# PowerRails.net
KiCad netlist of a schematic drawn in Altium Designer
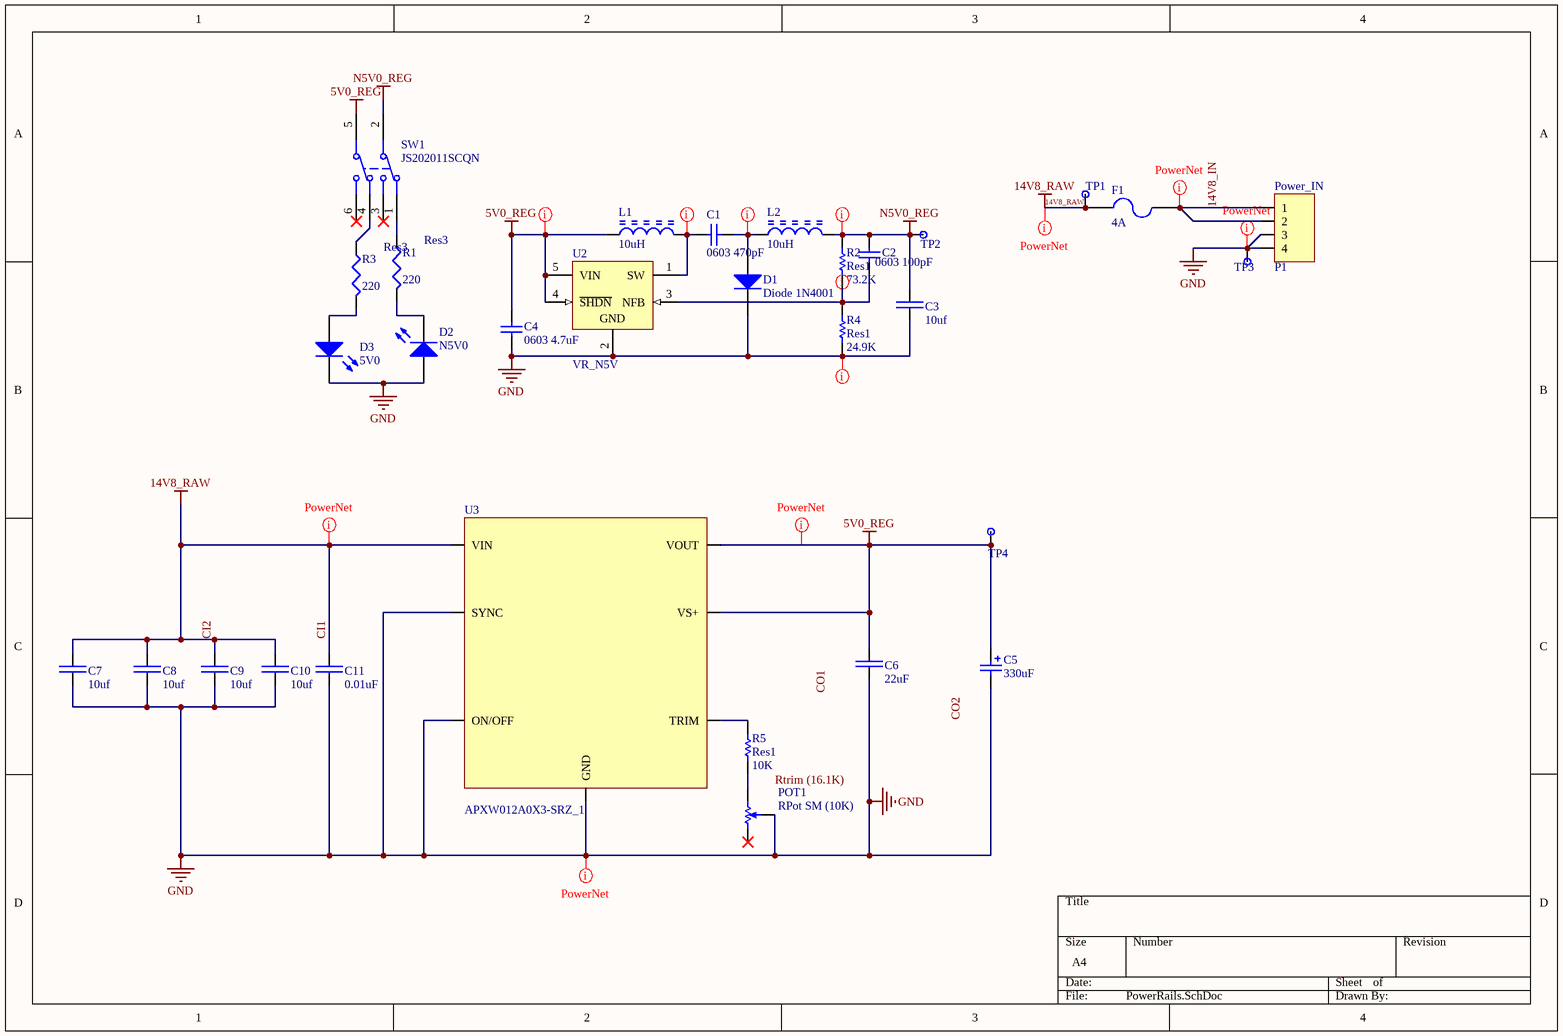
[diagram p0: PowerRails.SchDoc]

(export (version "E")
  (design (tool "Eeschema 10.0.6"))
  (components
    (comp (ref "C1")
      (value "0603 470pF")
      (footprint "CAPC1608X90X35LL10T15")
      (fields (field (name "PART NUMBER") "GRM188R61E475KE11D") (field (name "MANUFACTURER") "Murata"))
      (libsource (lib "Altium Content Vault") (part "CAP"))
    )
    (comp (ref "C2")
      (value "0603 100pF")
      (footprint "CAPC1608X90X35LL10T15")
      (fields (field (name "PART NUMBER") "GRM188R61E475KE11D") (field (name "MANUFACTURER") "Murata"))
      (libsource (lib "Altium Content Vault") (part "CAP"))
    )
    (comp (ref "C3")
      (value "10uf")
      (footprint "10uF capacitor LPB")
      (description "CAP CER 10UF 50V X5R 1206")
      (fields (field (name "TOLERANCE") "20%"))
      (libsource (lib "RSX_Capacitors") (part "GRT31CR61H106ME01L"))
    )
    (comp (ref "C4")
      (value "0603 4.7uF")
      (footprint "CAPC1608X90X35LL10T15")
      (fields (field (name "PART NUMBER") "GRM188R61E475KE11D") (field (name "MANUFACTURER") "Murata"))
      (libsource (lib "Altium Content Vault") (part "CAP"))
    )
    (comp (ref "C5")
      (value "330uF")
      (footprint "330uF throught hole")
      (description "CAP ALUM 330UF 20% 35V RADIAL")
      (fields (field (name "TOLERANCE") "20%"))
      (libsource (lib "RSX_Capacitors") (part "35ZLH330MEFCT810X12.5"))
    )
    (comp (ref "C6")
      (value "22uF")
      (footprint "22uF Capacitor")
      (description "Cap Ceramic 22uF 25V X7R 10% SMD 1210 125C Embossed T/R")
      (fields (field (name "TOLERANCE") "10%") (field (name "VOLTAGE") "25V"))
      (libsource (lib "RSX_Capacitors") (part "GRM32ER71E226KE15L"))
    )
    (comp (ref "C7")
      (value "10uf")
      (footprint "10uF capacitor LPB")
      (description "CAP CER 10UF 50V X5R 1206")
      (fields (field (name "TOLERANCE") "20%"))
      (libsource (lib "RSX_Capacitors") (part "GRT31CR61H106ME01L"))
    )
    (comp (ref "C8")
      (value "10uf")
      (footprint "10uF capacitor LPB")
      (description "CAP CER 10UF 50V X5R 1206")
      (fields (field (name "TOLERANCE") "20%"))
      (libsource (lib "RSX_Capacitors") (part "GRT31CR61H106ME01L"))
    )
    (comp (ref "C9")
      (value "10uf")
      (footprint "10uF capacitor LPB")
      (description "CAP CER 10UF 50V X5R 1206")
      (fields (field (name "TOLERANCE") "20%"))
      (libsource (lib "RSX_Capacitors") (part "GRT31CR61H106ME01L"))
    )
    (comp (ref "C10")
      (value "10uf")
      (footprint "10uF capacitor LPB")
      (description "CAP CER 10UF 50V X5R 1206")
      (fields (field (name "TOLERANCE") "20%"))
      (libsource (lib "RSX_Capacitors") (part "GRT31CR61H106ME01L"))
    )
    (comp (ref "C11")
      (value "0.01uF")
      (footprint "0.01uF capacitor")
      (description "Cap Ceramic 0.01uF 250V X7R 10% Pad SMD 0603 125C Automotive T/R")
      (fields (field (name "TOLERANCE") "10%"))
      (libsource (lib "RSX_Capacitors") (part "C0603C103KARACAUTO"))
    )
    (comp (ref "D1")
      (value "Diode 1N4001")
      (footprint "DO-41")
      (description "1 Amp General Purpose Rectifier")
      (fields (field (name "PUBLISHER") "Altium Limited"))
      (libsource (lib "Miscellaneous Devices") (part "Diode 1N4001"))
    )
    (comp (ref "D2")
      (value "N5V0")
      (footprint "LTST-C171TBKT")
      (libsource (lib "RSX_Diodes") (part "Blue LED"))
    )
    (comp (ref "D3")
      (value "5V0")
      (footprint "LTST-C171TBKT")
      (libsource (lib "RSX_Diodes") (part "Blue LED"))
    )
    (comp (ref "F1")
      (value "4A")
      (footprint "0157010.DR")
      (description "Fuse")
      (fields (field (name "PUBLISHER") "Altium Limited"))
      (libsource (lib "RSX_Miscellaneous") (part "Fuse 2"))
    )
    (comp (ref "L1")
      (value "10uH")
      (footprint "BOUR-CM322522_V")
      (description "Chip Inductor\r\n, 10 uH, +/- 10%, -40 to 125 degC, 1210 (3225 Metric), RoHS, Tape and Reel")
      (libsource (lib "Altium Content Vault") (part "BOUR-IND-2A"))
    )
    (comp (ref "L2")
      (value "10uH")
      (footprint "BOUR-CM322522_V")
      (description "Chip Inductor\r\n, 10 uH, +/- 10%, -40 to 125 degC, 1210 (3225 Metric), RoHS, Tape and Reel")
      (libsource (lib "Altium Content Vault") (part "BOUR-IND-2A"))
    )
    (comp (ref "P1")
      (value "Power_IN")
      (footprint "MOLEX 0039281043")
      (libsource (lib "RSX_Connectors") (part "Molex 0039281043"))
    )
    (comp (ref "POT1")
      (value "RPot SM (10K)")
      (footprint "POT4MM-2")
      (description "Square Trimming Potentiometer")
      (fields (field (name "PUBLISHER") "Altium Limited"))
      (libsource (lib "Miscellaneous Devices") (part "RPot SM"))
    )
    (comp (ref "R1")
      (value "Res3")
      (footprint "RESC1608X06N_0603")
      (description "Resistor")
      (fields (field (name "ALTIUM_VALUE") "220") (field (name "PUBLISHER") "Altium Limited"))
      (libsource (lib "RSX_Resistors") (part "Res3"))
    )
    (comp (ref "R2")
      (value "Res1")
      (footprint "RESC1608X06N_0603")
      (description "Resistor")
      (fields (field (name "ALTIUM_VALUE") "73.2K") (field (name "PUBLISHER") "Altium Limited"))
      (libsource (lib "RSX_Resistors") (part "Res1"))
    )
    (comp (ref "R3")
      (value "Res3")
      (footprint "RESC1608X06N_0603")
      (description "Resistor")
      (fields (field (name "ALTIUM_VALUE") "220") (field (name "PUBLISHER") "Altium Limited"))
      (libsource (lib "RSX_Resistors") (part "Res3"))
    )
    (comp (ref "R4")
      (value "Res1")
      (footprint "RESC1608X06N_0603")
      (description "Resistor")
      (fields (field (name "ALTIUM_VALUE") "24.9K") (field (name "PUBLISHER") "Altium Limited"))
      (libsource (lib "RSX_Resistors") (part "Res1"))
    )
    (comp (ref "R5")
      (value "Res1")
      (footprint "RESC1608X06N_0603")
      (description "Resistor")
      (fields (field (name "ALTIUM_VALUE") "10K") (field (name "PUBLISHER") "Altium Limited"))
      (libsource (lib "RSX_Resistors") (part "Res1"))
    )
    (comp (ref "SW1")
      (value "JS202011SCQN")
      (footprint "CKCP-JS202011SCQN-6_V")
      (description "Switch Slide DPDT, 0.3 A, 6 V, -40 to 85 degC, 6-Pin SMD, RoHS, Tape and Reel")
      (fields (field (name "MANUFACTURER") "C&K Components"))
      (libsource (lib "Altium Content Vault") (part "CKCP-JS202011SCQN-6"))
    )
    (comp (ref "TP1")
      (value "5V0_REG")
      (footprint "50_MIL_PAD")
      (libsource (lib "RSX_Test_Points") (part "TestPt"))
    )
    (comp (ref "TP2")
      (value "N5V0_REG")
      (footprint "50_MIL_PAD")
      (libsource (lib "RSX_Test_Points") (part "TestPt"))
    )
    (comp (ref "TP3")
      (value "12V0_RAW")
      (footprint "50_MIL_PAD")
      (libsource (lib "RSX_Test_Points") (part "TestPt"))
    )
    (comp (ref "TP4")
      (value "12V0_RAW")
      (footprint "50_MIL_PAD")
      (libsource (lib "RSX_Test_Points") (part "TestPt"))
    )
    (comp (ref "U2")
      (value "VR_N5V")
      (footprint "LT-S5-5-SOT-23_L")
      (fields
        (field (name "PARTNUMBER") "LT1617ES5#TRMPBF")
        (field (name "MANUFACTURER") "Linear Technology")
      )
      (libsource (lib "Altium Content Vault") (part "LT-LT161X_1931-S5-5"))
    )
    (comp (ref "U3")
      (value "APXW012A0X3-SRZ_1")
      (footprint "APXW012A0X3-SRZ")
      (description "DC DC CONVERTER 3-18V 12A")
      (libsource (lib "RSX_ICs") (part "APXW012A0X3-SRZ_1"))
    )
  )
  (nets
    (net (code "1") (name "/14V8_IN") (class "Default")
      (node (ref "F1") (pin "2") (pinfunction "2_2") (pintype "passive"))
      (node (ref "P1") (pin "1") (pinfunction "1_1") (pintype "passive"))
      (node (ref "P1") (pin "2") (pinfunction "2_2") (pintype "passive"))
    )
    (net (code "5") (name "5V0_REG") (class "Default")
      (node (ref "C4") (pin "2") (pinfunction "2_2") (pintype "passive"))
      (node (ref "C5") (pin "1") (pinfunction "1_1") (pintype "passive"))
      (node (ref "C6") (pin "2") (pinfunction "16_2") (pintype "passive"))
      (node (ref "L1") (pin "1") (pinfunction "1_1") (pintype "passive"))
      (node (ref "SW1") (pin "5") (pinfunction "COM_5") (pintype "passive"))
      (node (ref "TP4") (pin "1") (pinfunction "1_1") (pintype "passive"))
      (node (ref "U2") (pin "4") (pinfunction "~{SHDN}_4") (pintype "input"))
      (node (ref "U2") (pin "5") (pinfunction "VIN_5") (pintype "power_in"))
      (node (ref "U3") (pin "3") (pinfunction "VS+_3") (pintype "passive"))
      (node (ref "U3") (pin "5") (pinfunction "VOUT_5") (pintype "passive"))
    )
    (net (code "6") (name "14V8_RAW") (class "Default")
      (node (ref "C10") (pin "2") (pinfunction "16_2") (pintype "passive"))
      (node (ref "C11") (pin "2") (pinfunction "16_2") (pintype "passive"))
      (node (ref "C7") (pin "2") (pinfunction "16_2") (pintype "passive"))
      (node (ref "C8") (pin "2") (pinfunction "16_2") (pintype "passive"))
      (node (ref "C9") (pin "2") (pinfunction "16_2") (pintype "passive"))
      (node (ref "F1") (pin "1") (pinfunction "1_1") (pintype "passive"))
      (node (ref "TP1") (pin "1") (pinfunction "1_1") (pintype "passive"))
      (node (ref "U3") (pin "7") (pinfunction "VIN_7") (pintype "passive"))
    )
    (net (code "7") (name "GND") (class "Default")
      (node (ref "C10") (pin "1") (pinfunction "15_1") (pintype "passive"))
      (node (ref "C11") (pin "1") (pinfunction "15_1") (pintype "passive"))
      (node (ref "C3") (pin "1") (pinfunction "15_1") (pintype "passive"))
      (node (ref "C4") (pin "1") (pinfunction "1_1") (pintype "passive"))
      (node (ref "C5") (pin "2") (pinfunction "2_2") (pintype "passive"))
      (node (ref "C6") (pin "1") (pinfunction "15_1") (pintype "passive"))
      (node (ref "C7") (pin "1") (pinfunction "15_1") (pintype "passive"))
      (node (ref "C8") (pin "1") (pinfunction "15_1") (pintype "passive"))
      (node (ref "C9") (pin "1") (pinfunction "15_1") (pintype "passive"))
      (node (ref "D1") (pin "2") (pinfunction "K_2") (pintype "passive"))
      (node (ref "D2") (pin "1") (pinfunction "A_1") (pintype "passive"))
      (node (ref "D3") (pin "2") (pinfunction "K_2") (pintype "passive"))
      (node (ref "P1") (pin "3") (pinfunction "3_3") (pintype "passive"))
      (node (ref "P1") (pin "4") (pinfunction "4_4") (pintype "passive"))
      (node (ref "POT1") (pin "W") (pinfunction "W_W") (pintype "passive"))
      (node (ref "R4") (pin "1") (pinfunction "1_1") (pintype "passive"))
      (node (ref "TP3") (pin "1") (pinfunction "1_1") (pintype "passive"))
      (node (ref "U2") (pin "2") (pinfunction "GND_2") (pintype "power_in"))
      (node (ref "U3") (pin "1") (pinfunction "ON/OFF_1") (pintype "passive"))
      (node (ref "U3") (pin "2") (pinfunction "GND_2") (pintype "passive"))
      (node (ref "U3") (pin "6") (pinfunction "SYNC_6") (pintype "passive"))
    )
    (net (code "8") (name "N5V0_REG") (class "Default")
      (node (ref "C2") (pin "2") (pinfunction "2_2") (pintype "passive"))
      (node (ref "C3") (pin "2") (pinfunction "16_2") (pintype "passive"))
      (node (ref "L2") (pin "2") (pinfunction "2_2") (pintype "passive"))
      (node (ref "R2") (pin "2") (pinfunction "2_2") (pintype "passive"))
      (node (ref "SW1") (pin "2") (pinfunction "COM_2") (pintype "passive"))
      (node (ref "TP2") (pin "1") (pinfunction "1_1") (pintype "passive"))
    )
    (net (code "9") (name "Net-(D1-A)") (class "Default")
      (node (ref "C1") (pin "2") (pinfunction "2_2") (pintype "passive"))
      (node (ref "D1") (pin "1") (pinfunction "A_1") (pintype "passive"))
      (node (ref "L2") (pin "1") (pinfunction "1_1") (pintype "passive"))
    )
    (net (code "10") (name "Net-(D2-K)") (class "Default")
      (node (ref "D2") (pin "2") (pinfunction "K_2") (pintype "passive"))
      (node (ref "R1") (pin "2") (pinfunction "2_2") (pintype "passive"))
    )
    (net (code "11") (name "Net-(D3-A)") (class "Default")
      (node (ref "D3") (pin "1") (pinfunction "A_1") (pintype "passive"))
      (node (ref "R3") (pin "2") (pinfunction "2_2") (pintype "passive"))
    )
    (net (code "12") (name "Net-(POT1-+)") (class "Default")
      (node (ref "POT1") (pin "CW") (pinfunction "+_CW") (pintype "passive"))
      (node (ref "R5") (pin "1") (pinfunction "1_1") (pintype "passive"))
    )
    (net (code "13") (name "Net-(R1-Pad1)") (class "Default")
      (node (ref "R1") (pin "1") (pinfunction "1_1") (pintype "passive"))
      (node (ref "SW1") (pin "1") (pinfunction "1_1") (pintype "passive"))
    )
    (net (code "14") (name "Net-(R3-Pad1)") (class "Default")
      (node (ref "R3") (pin "1") (pinfunction "1_1") (pintype "passive"))
      (node (ref "SW1") (pin "4") (pinfunction "4_4") (pintype "passive"))
    )
    (net (code "15") (name "Net-(U2-NFB)") (class "Default")
      (node (ref "C2") (pin "1") (pinfunction "1_1") (pintype "passive"))
      (node (ref "R2") (pin "1") (pinfunction "1_1") (pintype "passive"))
      (node (ref "R4") (pin "2") (pinfunction "2_2") (pintype "passive"))
      (node (ref "U2") (pin "3") (pinfunction "NFB_3") (pintype "input"))
    )
    (net (code "16") (name "Net-(U2-SW)") (class "Default")
      (node (ref "C1") (pin "1") (pinfunction "1_1") (pintype "passive"))
      (node (ref "L1") (pin "2") (pinfunction "2_2") (pintype "passive"))
      (node (ref "U2") (pin "1") (pinfunction "SW_1") (pintype "power_in"))
    )
    (net (code "17") (name "Net-(U3-TRIM)") (class "Default")
      (node (ref "R5") (pin "2") (pinfunction "2_2") (pintype "passive"))
      (node (ref "U3") (pin "4") (pinfunction "TRIM_4") (pintype "passive"))
    )
    (net (code "18") (name "unconnected-(POT1---PadCCW)") (class "Default")
      (node (ref "POT1") (pin "CCW") (pinfunction "-_CCW") (pintype "passive+no_connect"))
    )
    (net (code "19") (name "unconnected-(SW1-Pad3)") (class "Default")
      (node (ref "SW1") (pin "3") (pinfunction "3_3") (pintype "passive+no_connect"))
    )
    (net (code "20") (name "unconnected-(SW1-Pad6)") (class "Default")
      (node (ref "SW1") (pin "6") (pinfunction "6_6") (pintype "passive+no_connect"))
    )
  )
)
